# schematic.net
KiCad netlist of a schematic drawn in EasyEDA
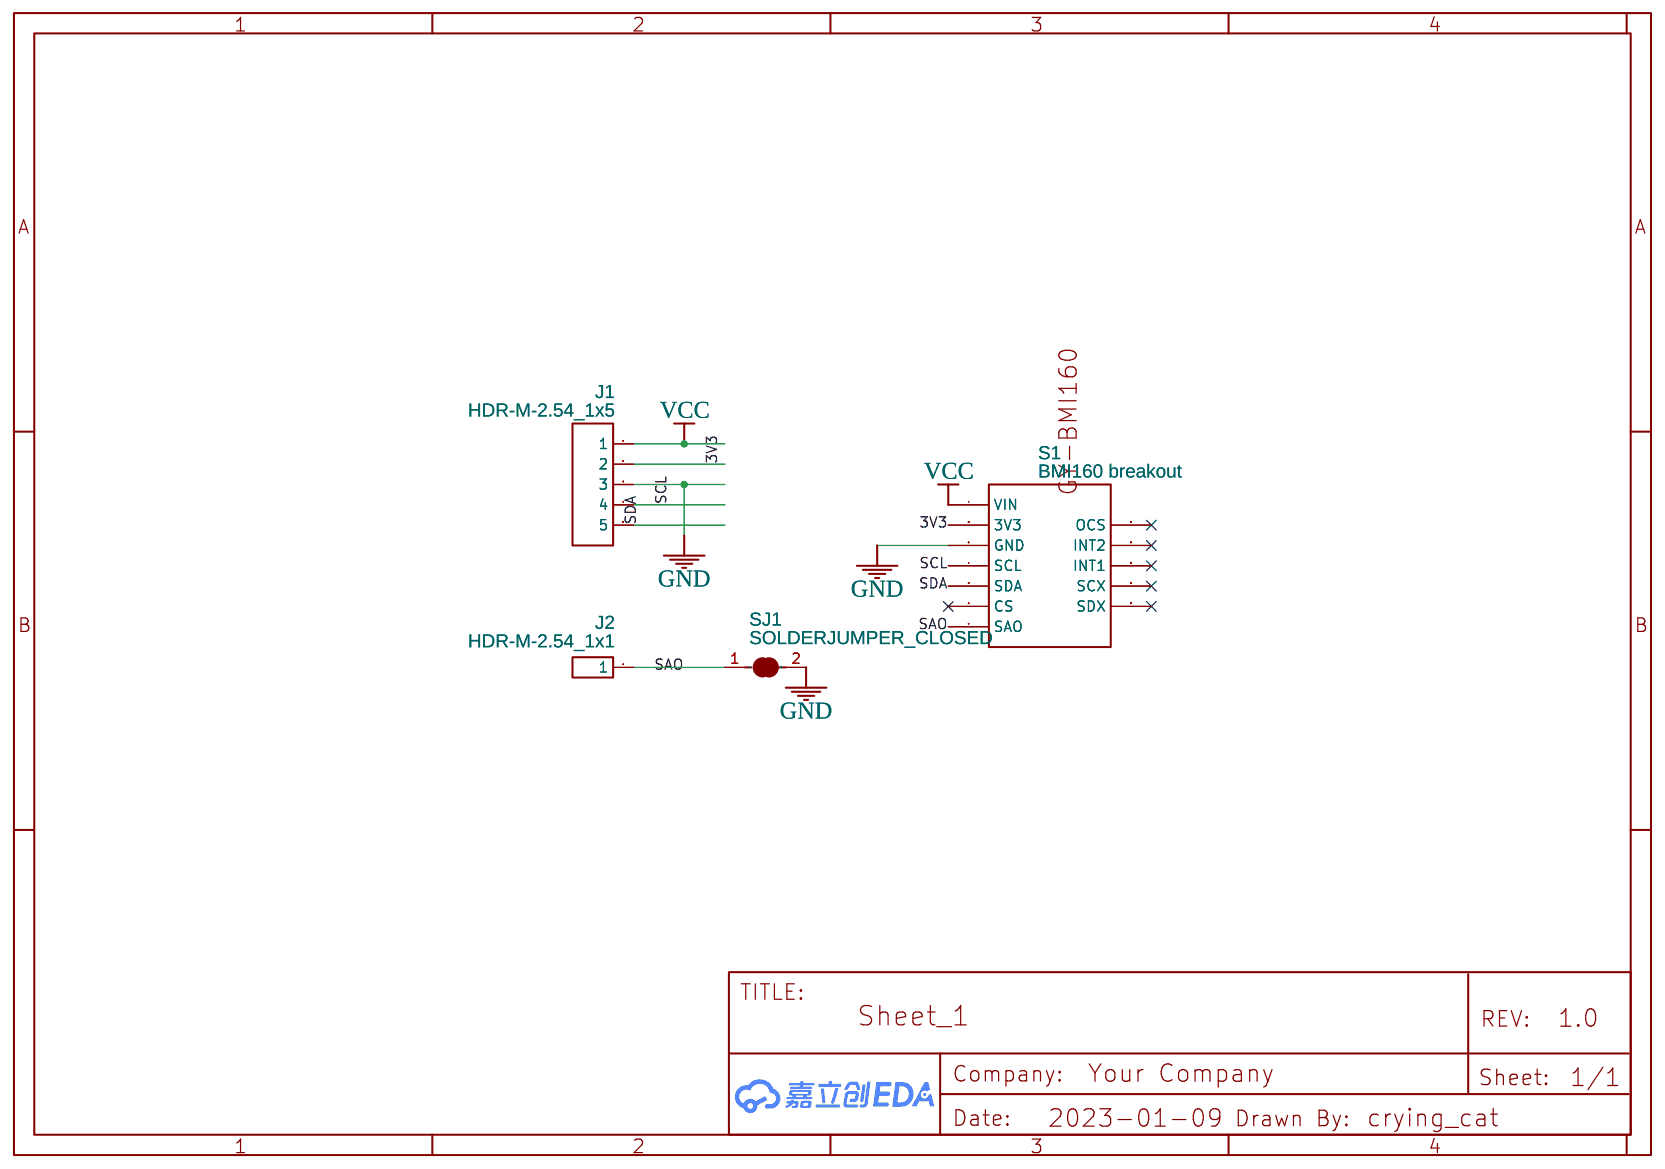
[diagram p0: schematic sheet]

(export (version "E")
  (design (tool "Eeschema 10.0.6"))
  (components
    (comp (ref "J1")
      (value "HDR-M-2.54_1x5")
      (fields (field (name "BOM_Supplier Part") "C358687"))
      (libsource (lib "") (part "HDR-M-2.54_1x5"))
    )
    (comp (ref "J2")
      (value "HDR-M-2.54_1x1")
      (fields (field (name "BOM_Supplier Part") "C81276"))
      (libsource (lib "") (part "HDR-M-2.54_1x1"))
    )
    (comp (ref "S1") (value "BMI160 breakout") (libsource (lib "") (part "BMI160 breakout")))
    (comp (ref "SJ1") (value "SOLDERJUMPER_CLOSED") (libsource (lib "") (part "SOLDERJUMPER_CLOSED")))
  )
  (nets
    (net (code "1") (name "/3V3") (class "Default")
      (node (ref "J1") (pin "2") (pinfunction "2_2") (pintype "unspecified"))
      (node (ref "S1") (pin "6") (pinfunction "3V3_6") (pintype "unspecified"))
    )
    (net (code "2") (name "/SAO") (class "Default")
      (node (ref "J2") (pin "1") (pinfunction "1_1") (pintype "input"))
      (node (ref "S1") (pin "1") (pinfunction "SAO_1") (pintype "unspecified"))
      (node (ref "SJ1") (pin "1") (pinfunction "1_1") (pintype "bidirectional"))
    )
    (net (code "3") (name "/SCL") (class "Default")
      (node (ref "J1") (pin "4") (pinfunction "4_4") (pintype "unspecified"))
      (node (ref "S1") (pin "4") (pinfunction "SCL_4") (pintype "unspecified"))
    )
    (net (code "4") (name "/SDA") (class "Default")
      (node (ref "J1") (pin "5") (pinfunction "5_5") (pintype "unspecified"))
      (node (ref "S1") (pin "3") (pinfunction "SDA_3") (pintype "unspecified"))
    )
    (net (code "5") (name "GND") (class "Default")
      (node (ref "J1") (pin "3") (pinfunction "3_3") (pintype "unspecified"))
      (node (ref "S1") (pin "5") (pinfunction "GND_5") (pintype "unspecified"))
      (node (ref "SJ1") (pin "2") (pinfunction "2_2") (pintype "bidirectional"))
    )
    (net (code "6") (name "VCC") (class "Default")
      (node (ref "J1") (pin "1") (pinfunction "1_1") (pintype "unspecified"))
      (node (ref "S1") (pin "7") (pinfunction "VIN_7") (pintype "unspecified"))
    )
    (net (code "7") (name "unconnected-(S1-CS-Pad2)") (class "Default")
      (node (ref "S1") (pin "2") (pinfunction "CS_2") (pintype "unspecified+no_connect"))
    )
    (net (code "8") (name "unconnected-(S1-INT1-Pad10)") (class "Default")
      (node (ref "S1") (pin "10") (pinfunction "INT1_10") (pintype "unspecified+no_connect"))
    )
    (net (code "9") (name "unconnected-(S1-INT2-Pad9)") (class "Default")
      (node (ref "S1") (pin "9") (pinfunction "INT2_9") (pintype "unspecified+no_connect"))
    )
    (net (code "10") (name "unconnected-(S1-OCS-Pad8)") (class "Default")
      (node (ref "S1") (pin "8") (pinfunction "OCS_8") (pintype "unspecified+no_connect"))
    )
    (net (code "11") (name "unconnected-(S1-SCX-Pad11)") (class "Default")
      (node (ref "S1") (pin "11") (pinfunction "SCX_11") (pintype "unspecified+no_connect"))
    )
    (net (code "12") (name "unconnected-(S1-SDX-Pad12)") (class "Default")
      (node (ref "S1") (pin "12") (pinfunction "SDX_12") (pintype "unspecified+no_connect"))
    )
  )
)
